# design.net
KiCad netlist of a schematic drawn in EAGLE
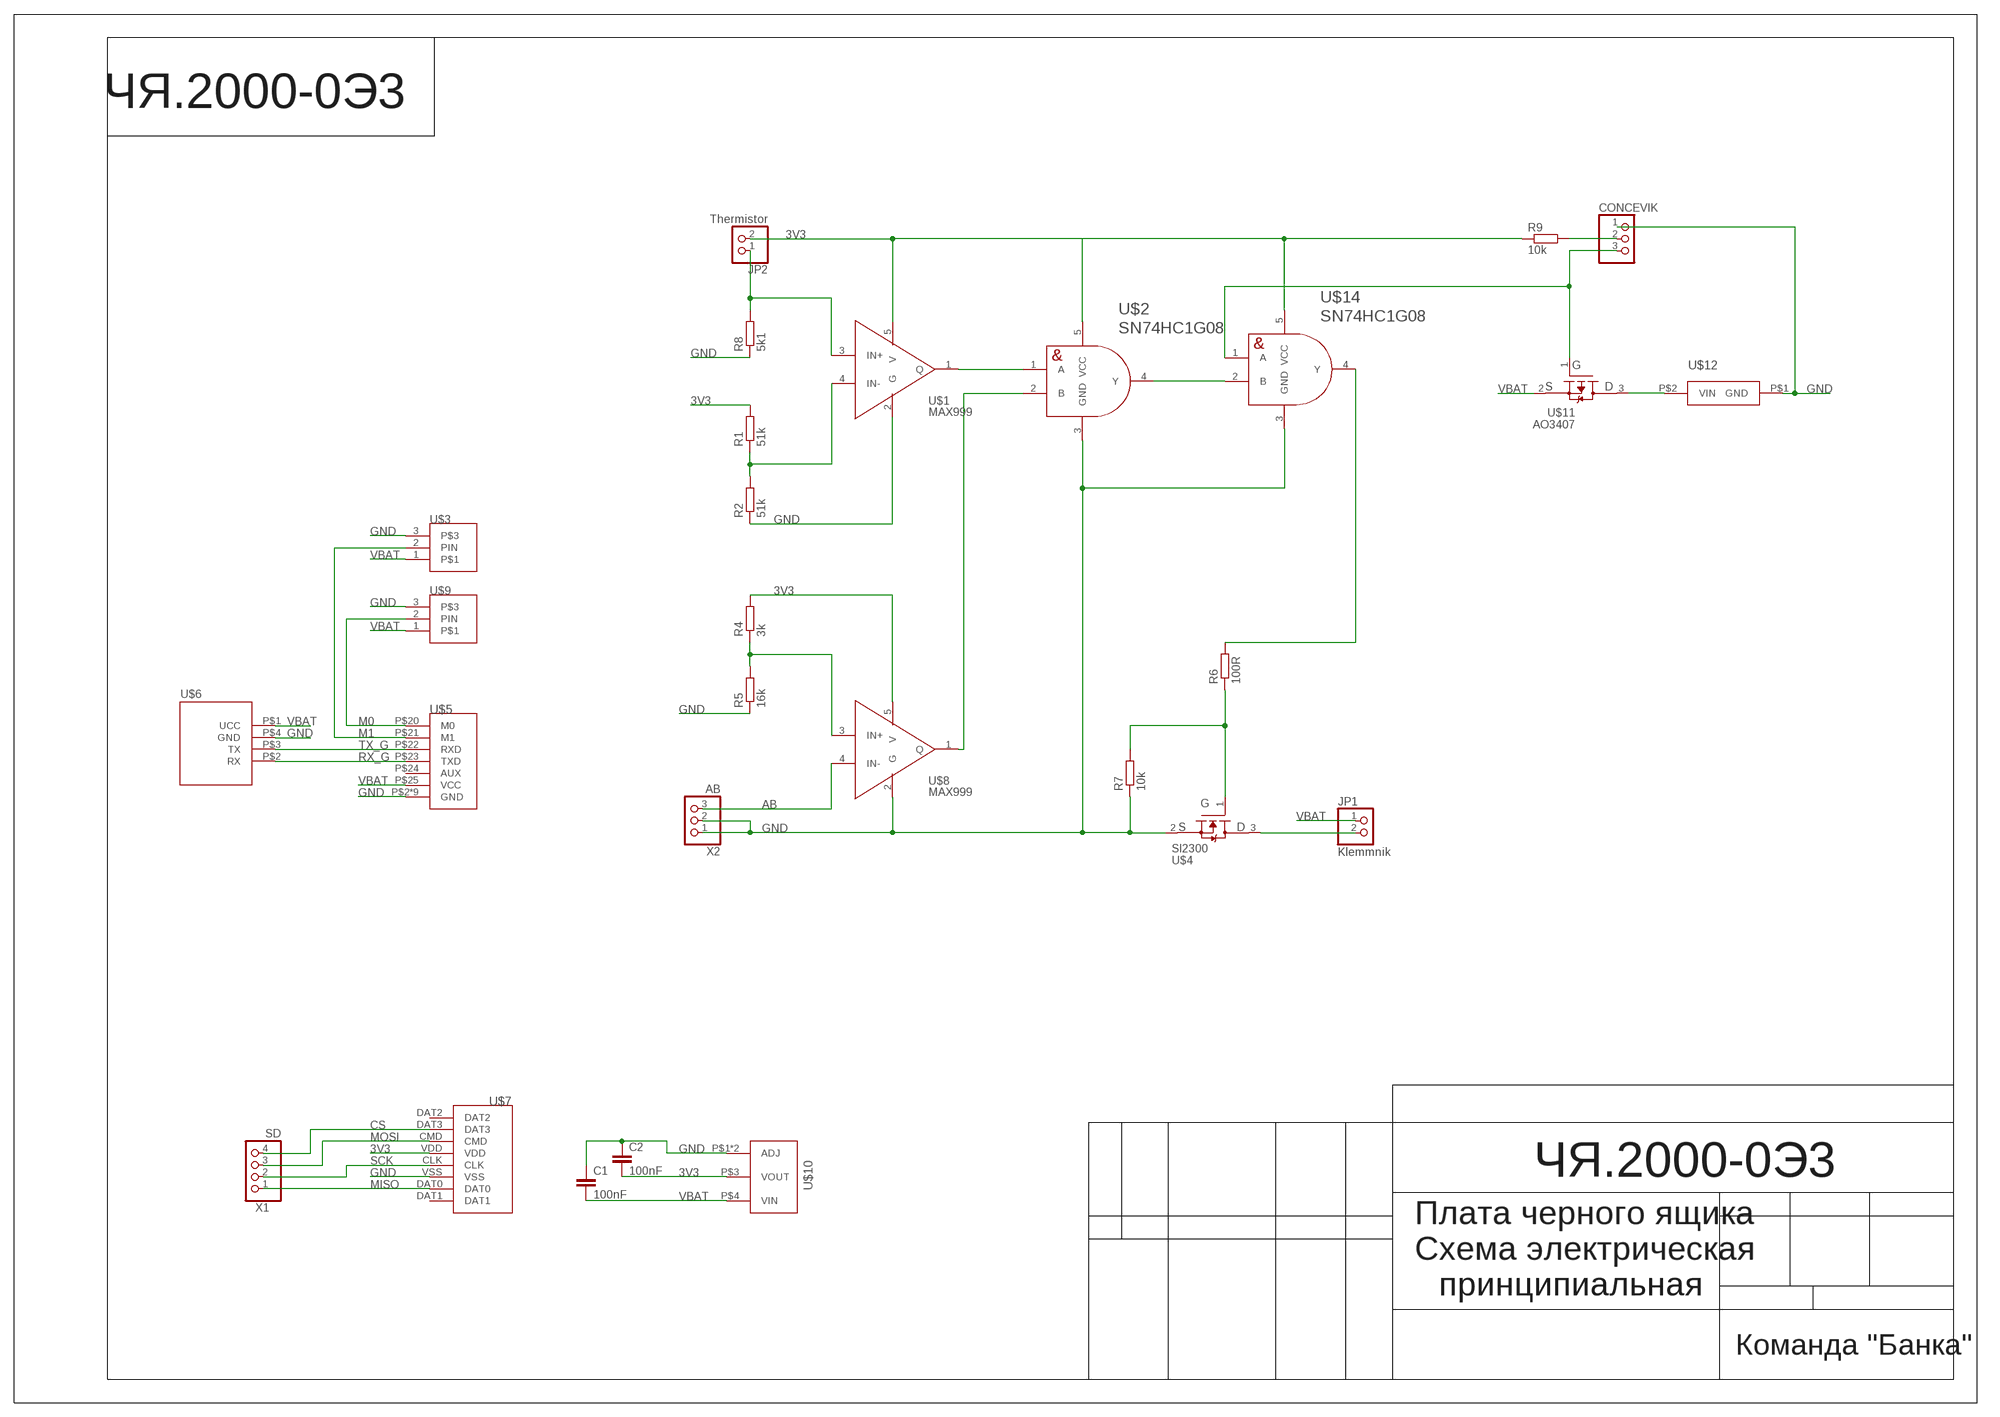
[diagram p0: schematic, sheet 1]

(export (version "E")
  (design (tool "Eeschema 10.0.6"))
  (components
    (comp (ref "C1")
      (value "100nF")
      (footprint "eagle-import:C0603")
      (libsource (lib "eagle-import") (part "C-EUC0603"))
    )
    (comp (ref "C2")
      (value "100nF")
      (footprint "eagle-import:C0603")
      (libsource (lib "eagle-import") (part "C-EUC0603"))
    )
    (comp (ref "CONCEVIK")
      (value "PINHD-1X3")
      (footprint "eagle-import:1X03")
      (libsource (lib "eagle-import") (part "PINHD-1X3"))
    )
    (comp (ref "JP1")
      (value "Klemmnik")
      (footprint "eagle-import:1X02")
      (libsource (lib "eagle-import") (part "PINHD-1X2"))
    )
    (comp (ref "JP2")
      (value "Thermistor")
      (footprint "eagle-import:1X02")
      (libsource (lib "eagle-import") (part "PINHD-1X2"))
    )
    (comp (ref "R1")
      (value "51k")
      (footprint "eagle-import:R0603")
      (libsource (lib "eagle-import") (part "R-EU_R0603"))
    )
    (comp (ref "R2")
      (value "51k")
      (footprint "eagle-import:R0603")
      (libsource (lib "eagle-import") (part "R-EU_R0603"))
    )
    (comp (ref "R4")
      (value "3k")
      (footprint "eagle-import:R0603")
      (libsource (lib "eagle-import") (part "R-EU_R0603"))
    )
    (comp (ref "R5")
      (value "16k")
      (footprint "eagle-import:R0603")
      (libsource (lib "eagle-import") (part "R-EU_R0603"))
    )
    (comp (ref "R6")
      (value "100R")
      (footprint "eagle-import:R0603")
      (libsource (lib "eagle-import") (part "R-EU_R0603"))
    )
    (comp (ref "R7")
      (value "10k")
      (footprint "eagle-import:R0603")
      (libsource (lib "eagle-import") (part "R-EU_R0603"))
    )
    (comp (ref "R8")
      (value "5k1")
      (footprint "eagle-import:R0603")
      (libsource (lib "eagle-import") (part "R-EU_R0603"))
    )
    (comp (ref "R9")
      (value "10k")
      (footprint "eagle-import:R0603")
      (libsource (lib "eagle-import") (part "R-EU_R0603"))
    )
    (comp (ref "U$1")
      (value "MAX999")
      (footprint "eagle-import:SOT23-5")
      (libsource (lib "eagle-import") (part "MAX999"))
    )
    (comp (ref "U$2")
      (value "SN74HC1G08")
      (footprint "eagle-import:SOT23-5")
      (libsource (lib "eagle-import") (part "SN74HC1G08"))
    )
    (comp (ref "U$3")
      (value "CONNECT_3")
      (footprint "eagle-import:CONNECT_3")
      (libsource (lib "eagle-import") (part "CONNECT_3"))
    )
    (comp (ref "U$4")
      (value "SI2300")
      (footprint "eagle-import:SOT23-3")
      (libsource (lib "eagle-import") (part "SI2300"))
    )
    (comp (ref "U$5")
      (value "E220-400T22S")
      (footprint "eagle-import:E220-400T22S")
      (libsource (lib "eagle-import") (part "E220-400T22S"))
    )
    (comp (ref "U$6")
      (value "GPS-NEO7M")
      (footprint "eagle-import:GPS-NEO7M")
      (libsource (lib "eagle-import") (part "GPS-NEO7M"))
    )
    (comp (ref "U$7") (value "SD") (footprint "eagle-import:SD") (libsource (lib "eagle-import") (part "SD")))
    (comp (ref "U$8")
      (value "MAX999")
      (footprint "eagle-import:SOT23-5")
      (libsource (lib "eagle-import") (part "MAX999"))
    )
    (comp (ref "U$9")
      (value "CONNECT_3")
      (footprint "eagle-import:CONNECT_3")
      (libsource (lib "eagle-import") (part "CONNECT_3"))
    )
    (comp (ref "U$10")
      (value "AMS1117")
      (footprint "eagle-import:SOT223")
      (libsource (lib "eagle-import") (part "AMS1117"))
    )
    (comp (ref "U$11")
      (value "AO3407")
      (footprint "eagle-import:SOT23-3")
      (libsource (lib "eagle-import") (part "AO3407"))
    )
    (comp (ref "U$12")
      (value "BUZZERS8R6")
      (footprint "eagle-import:BUZZER-S8R12")
      (libsource (lib "eagle-import") (part "BUZZERS8R6"))
    )
    (comp (ref "U$14")
      (value "SN74HC1G08")
      (footprint "eagle-import:SOT23-5")
      (libsource (lib "eagle-import") (part "SN74HC1G08"))
    )
    (comp (ref "X1")
      (value "SD")
      (footprint "eagle-import:1X04")
      (libsource (lib "eagle-import") (part "PINHD-1X4"))
    )
    (comp (ref "X2")
      (value "AB")
      (footprint "eagle-import:1X03")
      (libsource (lib "eagle-import") (part "PINHD-1X3"))
    )
  )
  (nets
    (net (code "1") (name "/3V3") (class "Default")
      (node (ref "C2") (pin "2") (pinfunction "2_2") (pintype "passive"))
      (node (ref "JP2") (pin "2") (pinfunction "2_2") (pintype "passive"))
      (node (ref "R1") (pin "2") (pinfunction "2_2") (pintype "passive"))
      (node (ref "R4") (pin "2") (pinfunction "2_2") (pintype "passive"))
      (node (ref "R9") (pin "2") (pinfunction "2_2") (pintype "passive"))
      (node (ref "U$1") (pin "5") (pinfunction "V_5") (pintype "bidirectional"))
      (node (ref "U$10") (pin "P$3") (pinfunction "VOUT_P$3") (pintype "bidirectional"))
      (node (ref "U$14") (pin "5") (pinfunction "VCC_5") (pintype "bidirectional"))
      (node (ref "U$2") (pin "5") (pinfunction "VCC_5") (pintype "bidirectional"))
      (node (ref "U$7") (pin "VDD") (pinfunction "VDD_VDD") (pintype "bidirectional"))
      (node (ref "U$8") (pin "5") (pinfunction "V_5") (pintype "bidirectional"))
    )
    (net (code "2") (name "/AB") (class "Default")
      (node (ref "U$8") (pin "4") (pinfunction "IN-_4") (pintype "bidirectional"))
      (node (ref "X2") (pin "3") (pinfunction "3_3") (pintype "passive"))
    )
    (net (code "3") (name "/CS") (class "Default")
      (node (ref "U$7") (pin "DAT3") (pinfunction "DAT3_DAT3") (pintype "bidirectional"))
      (node (ref "X1") (pin "4") (pinfunction "4_4") (pintype "passive"))
    )
    (net (code "4") (name "/GND") (class "Default")
      (node (ref "C1") (pin "1") (pinfunction "1_1") (pintype "passive"))
      (node (ref "C2") (pin "1") (pinfunction "1_1") (pintype "passive"))
      (node (ref "CONCEVIK") (pin "1") (pinfunction "1_1") (pintype "passive"))
      (node (ref "R2") (pin "1") (pinfunction "1_1") (pintype "passive"))
      (node (ref "R5") (pin "1") (pinfunction "1_1") (pintype "passive"))
      (node (ref "R7") (pin "1") (pinfunction "1_1") (pintype "passive"))
      (node (ref "R8") (pin "1") (pinfunction "1_1") (pintype "passive"))
      (node (ref "U$1") (pin "2") (pinfunction "G_2") (pintype "bidirectional"))
      (node (ref "U$10") (pin "P$1") (pinfunction "ADJ_P$1") (pintype "bidirectional"))
      (node (ref "U$10") (pin "P$2") (pinfunction "ADJ_P$2") (pintype "bidirectional"))
      (node (ref "U$12") (pin "P$1") (pinfunction "GND_P$1") (pintype "bidirectional"))
      (node (ref "U$14") (pin "3") (pinfunction "GND_3") (pintype "bidirectional"))
      (node (ref "U$2") (pin "3") (pinfunction "GND_3") (pintype "bidirectional"))
      (node (ref "U$3") (pin "3") (pinfunction "P$3_3") (pintype "bidirectional"))
      (node (ref "U$4") (pin "2") (pinfunction "NS_2") (pintype "passive"))
      (node (ref "U$5") (pin "P$11") (pinfunction "GND_P$11") (pintype "bidirectional"))
      (node (ref "U$5") (pin "P$13") (pinfunction "GND_P$13") (pintype "bidirectional"))
      (node (ref "U$5") (pin "P$14") (pinfunction "GND_P$14") (pintype "bidirectional"))
      (node (ref "U$5") (pin "P$15") (pinfunction "GND_P$15") (pintype "bidirectional"))
      (node (ref "U$5") (pin "P$16") (pinfunction "GND_P$16") (pintype "bidirectional"))
      (node (ref "U$5") (pin "P$19") (pinfunction "GND_P$19") (pintype "bidirectional"))
      (node (ref "U$5") (pin "P$2") (pinfunction "GND_P$2") (pintype "bidirectional"))
      (node (ref "U$5") (pin "P$26") (pinfunction "GND_P$26") (pintype "bidirectional"))
      (node (ref "U$5") (pin "P$8") (pinfunction "GND_P$8") (pintype "bidirectional"))
      (node (ref "U$6") (pin "P$4") (pinfunction "GND_P$4") (pintype "bidirectional"))
      (node (ref "U$7") (pin "VSS") (pinfunction "VSS_VSS") (pintype "bidirectional"))
      (node (ref "U$8") (pin "2") (pinfunction "G_2") (pintype "bidirectional"))
      (node (ref "U$9") (pin "3") (pinfunction "P$3_3") (pintype "bidirectional"))
      (node (ref "X2") (pin "1") (pinfunction "1_1") (pintype "passive"))
      (node (ref "X2") (pin "2") (pinfunction "2_2") (pintype "passive"))
    )
    (net (code "5") (name "/M0") (class "Default")
      (node (ref "U$5") (pin "P$20") (pinfunction "M0_P$20") (pintype "bidirectional"))
      (node (ref "U$9") (pin "2") (pinfunction "PIN_2") (pintype "bidirectional"))
    )
    (net (code "6") (name "/M1") (class "Default")
      (node (ref "U$3") (pin "2") (pinfunction "PIN_2") (pintype "bidirectional"))
      (node (ref "U$5") (pin "P$21") (pinfunction "M1_P$21") (pintype "bidirectional"))
    )
    (net (code "7") (name "/MISO") (class "Default")
      (node (ref "U$7") (pin "DAT0") (pinfunction "DAT0_DAT0") (pintype "bidirectional"))
      (node (ref "X1") (pin "1") (pinfunction "1_1") (pintype "passive"))
    )
    (net (code "8") (name "/MOSI") (class "Default")
      (node (ref "U$7") (pin "CMD") (pinfunction "CMD_CMD") (pintype "bidirectional"))
      (node (ref "X1") (pin "3") (pinfunction "3_3") (pintype "passive"))
    )
    (net (code "9") (name "/RX_G") (class "Default")
      (node (ref "U$5") (pin "P$23") (pinfunction "TXD_P$23") (pintype "bidirectional"))
      (node (ref "U$6") (pin "P$2") (pinfunction "RX_P$2") (pintype "bidirectional"))
    )
    (net (code "10") (name "/SCK") (class "Default")
      (node (ref "U$7") (pin "CLK") (pinfunction "CLK_CLK") (pintype "bidirectional"))
      (node (ref "X1") (pin "2") (pinfunction "2_2") (pintype "passive"))
    )
    (net (code "11") (name "/TX_G") (class "Default")
      (node (ref "U$5") (pin "P$22") (pinfunction "RXD_P$22") (pintype "bidirectional"))
      (node (ref "U$6") (pin "P$3") (pinfunction "TX_P$3") (pintype "bidirectional"))
    )
    (net (code "12") (name "/VBAT") (class "Default")
      (node (ref "C1") (pin "2") (pinfunction "2_2") (pintype "passive"))
      (node (ref "JP1") (pin "1") (pinfunction "1_1") (pintype "passive"))
      (node (ref "U$10") (pin "P$4") (pinfunction "VIN_P$4") (pintype "bidirectional"))
      (node (ref "U$11") (pin "2") (pinfunction "PS_2") (pintype "passive"))
      (node (ref "U$3") (pin "1") (pinfunction "P$1_1") (pintype "bidirectional"))
      (node (ref "U$5") (pin "P$25") (pinfunction "VCC_P$25") (pintype "bidirectional"))
      (node (ref "U$6") (pin "P$1") (pinfunction "UCC_P$1") (pintype "bidirectional"))
      (node (ref "U$9") (pin "1") (pinfunction "P$1_1") (pintype "bidirectional"))
    )
    (net (code "13") (name "Net-(CONCEVIK-Pad2)") (class "Default")
      (node (ref "CONCEVIK") (pin "2") (pinfunction "2_2") (pintype "passive"))
      (node (ref "R9") (pin "1") (pinfunction "1_1") (pintype "passive"))
    )
    (net (code "14") (name "Net-(U$1-IN+)") (class "Default")
      (node (ref "JP2") (pin "1") (pinfunction "1_1") (pintype "passive"))
      (node (ref "R8") (pin "2") (pinfunction "2_2") (pintype "passive"))
      (node (ref "U$1") (pin "3") (pinfunction "IN+_3") (pintype "bidirectional"))
    )
    (net (code "15") (name "Net-(U$1-IN-)") (class "Default")
      (node (ref "R1") (pin "1") (pinfunction "1_1") (pintype "passive"))
      (node (ref "R2") (pin "2") (pinfunction "2_2") (pintype "passive"))
      (node (ref "U$1") (pin "4") (pinfunction "IN-_4") (pintype "bidirectional"))
    )
    (net (code "16") (name "Net-(U$1-Q)") (class "Default")
      (node (ref "U$1") (pin "1") (pinfunction "Q_1") (pintype "bidirectional"))
      (node (ref "U$2") (pin "1") (pinfunction "A_1") (pintype "bidirectional"))
    )
    (net (code "17") (name "Net-(U$2-B)") (class "Default")
      (node (ref "U$2") (pin "2") (pinfunction "B_2") (pintype "bidirectional"))
      (node (ref "U$8") (pin "1") (pinfunction "Q_1") (pintype "bidirectional"))
    )
    (net (code "18") (name "Net-(U$4-ND)") (class "Default")
      (node (ref "JP1") (pin "2") (pinfunction "2_2") (pintype "passive"))
      (node (ref "U$4") (pin "3") (pinfunction "ND_3") (pintype "passive"))
    )
    (net (code "19") (name "Net-(U$4-NG)") (class "Default")
      (node (ref "R6") (pin "1") (pinfunction "1_1") (pintype "passive"))
      (node (ref "R7") (pin "2") (pinfunction "2_2") (pintype "passive"))
      (node (ref "U$4") (pin "1") (pinfunction "NG_1") (pintype "passive"))
    )
    (net (code "20") (name "Net-(U$8-IN+)") (class "Default")
      (node (ref "R4") (pin "1") (pinfunction "1_1") (pintype "passive"))
      (node (ref "R5") (pin "2") (pinfunction "2_2") (pintype "passive"))
      (node (ref "U$8") (pin "3") (pinfunction "IN+_3") (pintype "bidirectional"))
    )
    (net (code "21") (name "Net-(U$11-PD)") (class "Default")
      (node (ref "U$11") (pin "3") (pinfunction "PD_3") (pintype "passive"))
      (node (ref "U$12") (pin "P$2") (pinfunction "VIN_P$2") (pintype "bidirectional"))
    )
    (net (code "22") (name "Net-(U$11-PG)") (class "Default")
      (node (ref "CONCEVIK") (pin "3") (pinfunction "3_3") (pintype "passive"))
      (node (ref "U$11") (pin "1") (pinfunction "PG_1") (pintype "passive"))
      (node (ref "U$14") (pin "1") (pinfunction "A_1") (pintype "bidirectional"))
    )
    (net (code "23") (name "Net-(U$14-B)") (class "Default")
      (node (ref "U$14") (pin "2") (pinfunction "B_2") (pintype "bidirectional"))
      (node (ref "U$2") (pin "4") (pinfunction "Y_4") (pintype "bidirectional"))
    )
    (net (code "24") (name "Net-(U$14-Y)") (class "Default")
      (node (ref "R6") (pin "2") (pinfunction "2_2") (pintype "passive"))
      (node (ref "U$14") (pin "4") (pinfunction "Y_4") (pintype "bidirectional"))
    )
    (net (code "25") (name "unconnected-(U$5-AUX-PadP$24)") (class "Default")
      (node (ref "U$5") (pin "P$24") (pinfunction "AUX_P$24") (pintype "bidirectional"))
    )
    (net (code "26") (name "unconnected-(U$7-PadDAT1)") (class "Default")
      (node (ref "U$7") (pin "DAT1") (pinfunction "DAT1_DAT1") (pintype "bidirectional"))
    )
    (net (code "27") (name "unconnected-(U$7-PadDAT2)") (class "Default")
      (node (ref "U$7") (pin "DAT2") (pinfunction "DAT2_DAT2") (pintype "bidirectional"))
    )
  )
)
